# MCU.net
KiCad netlist of a schematic drawn in Altium Designer
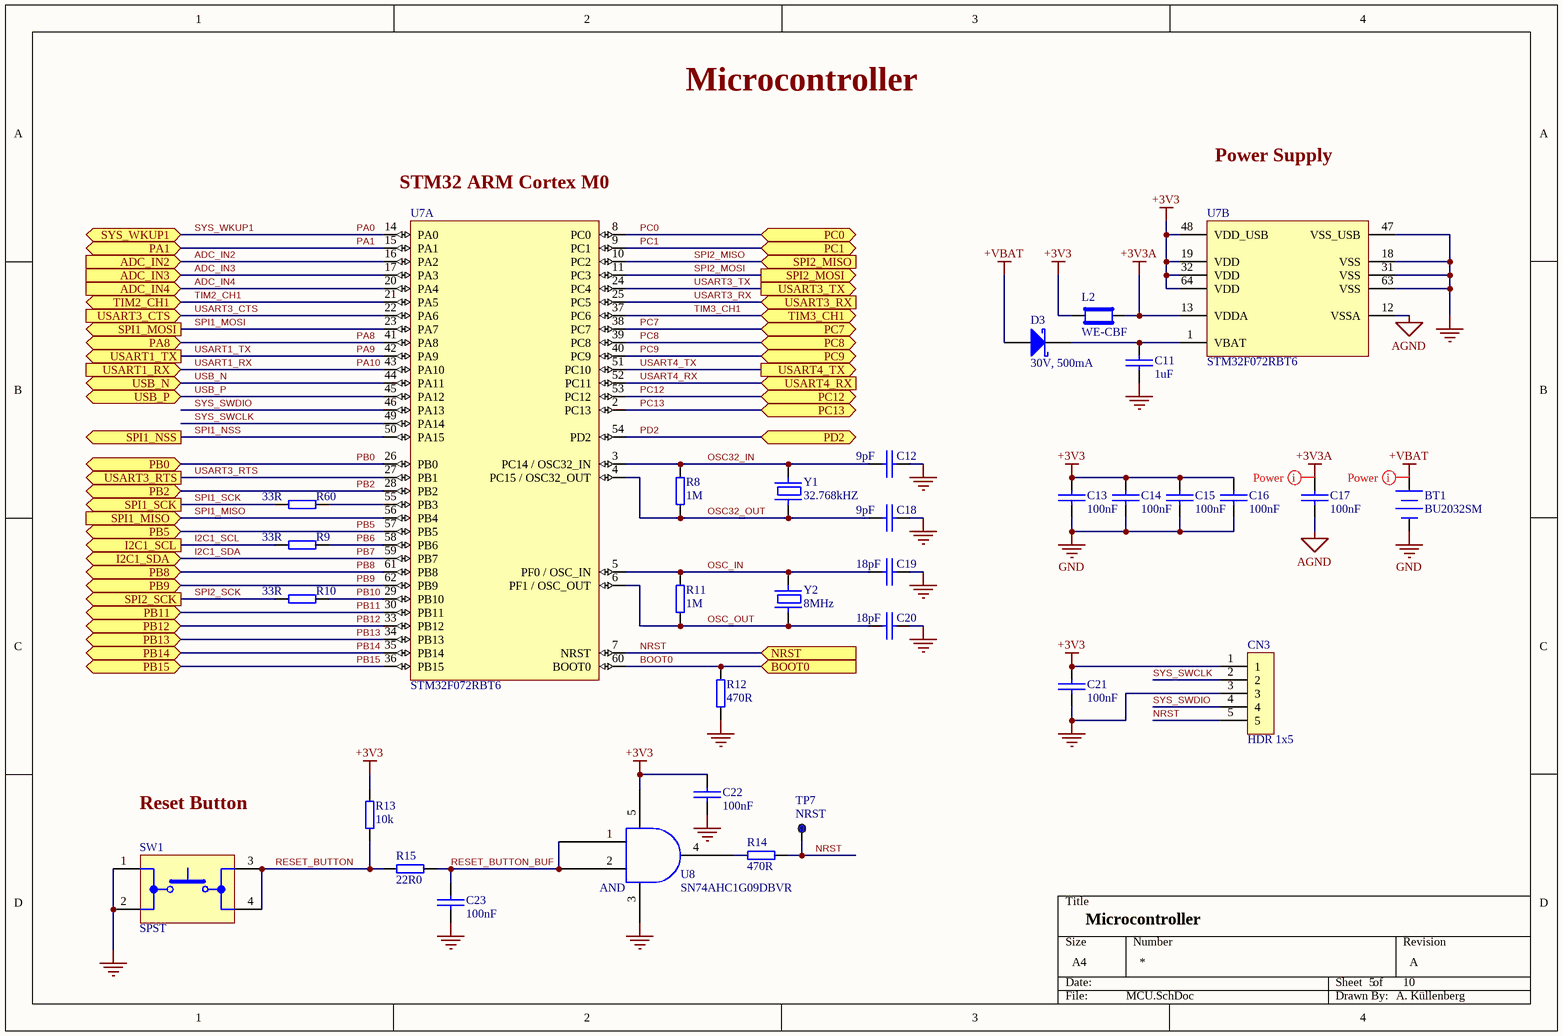
[diagram p0: MCU.SchDoc]

(export (version "E")
  (design (tool "Eeschema 10.0.6"))
  (components
    (comp (ref "BT1")
      (value "BU2032SM")
      (footprint "BU2032SM")
      (description "HOLDER CR2032 GOLD LEADS SMD")
      (fields
        (field (name "PART NUMBER") "BU2032SM-BT-GTR")
        (field (name "MANUFACTURER") "MPD (Memory Protection Devices)")
        (field (name "PUBLISHER") "Altium Limited")
      )
      (libsource (lib "AKLib") (part "Battery"))
    )
    (comp (ref "C11")
      (value "1uF")
      (footprint "C0603")
      (description "CAP CER 1UF 25V X7R 0603")
      (fields
        (field (name "PART NUMBER") "GCM188R71E105KA64D")
        (field (name "MANUFACTURER") "Murata Electronics North America")
      )
      (libsource (lib "AKLib") (part "CAP"))
    )
    (comp (ref "C12")
      (value "9pF")
      (footprint "C0603")
      (description "CAP CER 9PF 50V NP0 0603")
      (fields
        (field (name "PART NUMBER") "CL10C090DB8NNNC")
        (field (name "MANUFACTURER") "Samsung Electro-Mechanics America, Inc.")
      )
      (libsource (lib "AKLib") (part "CAP"))
    )
    (comp (ref "C13")
      (value "100nF")
      (footprint "C0603")
      (description "CAP CER 0.1UF 50V X7R 0603")
      (fields (field (name "PART NUMBER") "C0603C104K5RACTU") (field (name "MANUFACTURER") "Kemet"))
      (libsource (lib "AKLib") (part "CAP"))
    )
    (comp (ref "C14")
      (value "100nF")
      (footprint "C0603")
      (description "CAP CER 0.1UF 50V X7R 0603")
      (fields (field (name "PART NUMBER") "C0603C104K5RACTU") (field (name "MANUFACTURER") "Kemet"))
      (libsource (lib "AKLib") (part "CAP"))
    )
    (comp (ref "C15")
      (value "100nF")
      (footprint "C0603")
      (description "CAP CER 0.1UF 50V X7R 0603")
      (fields (field (name "PART NUMBER") "C0603C104K5RACTU") (field (name "MANUFACTURER") "Kemet"))
      (libsource (lib "AKLib") (part "CAP"))
    )
    (comp (ref "C16")
      (value "100nF")
      (footprint "C0603")
      (description "CAP CER 0.1UF 50V X7R 0603")
      (fields (field (name "PART NUMBER") "C0603C104K5RACTU") (field (name "MANUFACTURER") "Kemet"))
      (libsource (lib "AKLib") (part "CAP"))
    )
    (comp (ref "C17")
      (value "100nF")
      (footprint "C0603")
      (description "CAP CER 0.1UF 50V X7R 0603")
      (fields (field (name "PART NUMBER") "C0603C104K5RACTU") (field (name "MANUFACTURER") "Kemet"))
      (libsource (lib "AKLib") (part "CAP"))
    )
    (comp (ref "C18")
      (value "9pF")
      (footprint "C0603")
      (description "CAP CER 9PF 50V NP0 0603")
      (fields
        (field (name "PART NUMBER") "CL10C090DB8NNNC")
        (field (name "MANUFACTURER") "Samsung Electro-Mechanics America, Inc.")
      )
      (libsource (lib "AKLib") (part "CAP"))
    )
    (comp (ref "C19")
      (value "18pF")
      (footprint "C0603")
      (description "CAP CER 18PF 50V NP0 0603")
      (fields
        (field (name "PART NUMBER") "CL10C180JB8NNNC")
        (field (name "MANUFACTURER") "Samsung Electro-Mechanics America, Inc.")
      )
      (libsource (lib "AKLib") (part "CAP"))
    )
    (comp (ref "C20")
      (value "18pF")
      (footprint "C0603")
      (description "CAP CER 18PF 50V NP0 0603")
      (fields
        (field (name "PART NUMBER") "CL10C180JB8NNNC")
        (field (name "MANUFACTURER") "Samsung Electro-Mechanics America, Inc.")
      )
      (libsource (lib "AKLib") (part "CAP"))
    )
    (comp (ref "C21")
      (value "100nF")
      (footprint "C0603")
      (description "CAP CER 0.1UF 50V X7R 0603")
      (fields (field (name "PART NUMBER") "C0603C104K5RACTU") (field (name "MANUFACTURER") "Kemet"))
      (libsource (lib "AKLib") (part "CAP"))
    )
    (comp (ref "C22")
      (value "100nF")
      (footprint "C0603")
      (description "CAP CER 0.1UF 50V X7R 0603")
      (fields (field (name "PART NUMBER") "C0603C104K5RACTU") (field (name "MANUFACTURER") "Kemet"))
      (libsource (lib "AKLib") (part "CAP"))
    )
    (comp (ref "C23")
      (value "100nF")
      (footprint "C0603")
      (description "CAP CER 0.1UF 50V X7R 0603")
      (fields (field (name "PART NUMBER") "C0603C104K5RACTU") (field (name "MANUFACTURER") "Kemet"))
      (libsource (lib "AKLib") (part "CAP"))
    )
    (comp (ref "CN3")
      (value "HDR 1x5")
      (footprint "PREC005SAAN-RC")
      (description "CONN HEADER .100\" SNGL STR 5POS")
      (fields
        (field (name "PART NUMBER") "PREC005SAAN-RC")
        (field (name "MANUFACTURER") "Sullins Connector Solutions")
      )
      (libsource (lib "AKLib") (part "Header 1x5"))
    )
    (comp (ref "D3")
      (value "30V, 500mA")
      (footprint "SOD523_N")
      (description "DIODE SCHOTTKY 30V 500MA SC79-2")
      (fields
        (field (name "PART NUMBER") "BAS 3005B-02V H6327")
        (field (name "MANUFACTURER") "Infineon Technologies")
      )
      (libsource (lib "AKLib") (part "Schottky Diode"))
    )
    (comp (ref "L2")
      (value "WE-CBF")
      (footprint "L0603")
      (description "FERRITE BEAD 600 OHM 0603 1LN")
      (fields (field (name "PART NUMBER") "742792651") (field (name "MANUFACTURER") "Wurth Electronics Inc."))
      (libsource (lib "AKLib") (part "FBEAD"))
    )
    (comp (ref "R8")
      (value "1M")
      (footprint "R0603")
      (description "RES SMD 1M OHM 1% 1/10W 0603")
      (fields (field (name "PART NUMBER") "RC0603FR-071ML") (field (name "MANUFACTURER") "Yageo"))
      (libsource (lib "AKLib") (part "RES"))
    )
    (comp (ref "R9")
      (value "33R")
      (footprint "R0402")
      (description "RES SMD 33 OHM 1% 1/16W 0402")
      (fields (field (name "PART NUMBER") "RC0402FR-0733RL") (field (name "MANUFACTURER") "Yageo"))
      (libsource (lib "AKLib") (part "RES"))
    )
    (comp (ref "R10")
      (value "33R")
      (footprint "R0402")
      (description "RES SMD 33 OHM 1% 1/16W 0402")
      (fields (field (name "PART NUMBER") "RC0402FR-0733RL") (field (name "MANUFACTURER") "Yageo"))
      (libsource (lib "AKLib") (part "RES"))
    )
    (comp (ref "R11")
      (value "1M")
      (footprint "R0603")
      (description "RES SMD 1M OHM 1% 1/10W 0603")
      (fields (field (name "PART NUMBER") "RC0603FR-071ML") (field (name "MANUFACTURER") "Yageo"))
      (libsource (lib "AKLib") (part "RES"))
    )
    (comp (ref "R12")
      (value "470R")
      (footprint "R0402")
      (description "RES SMD 470 OHM 1% 1/16W 0402")
      (fields (field (name "PART NUMBER") "RC0402FR-07470RL") (field (name "MANUFACTURER") "Yageo"))
      (libsource (lib "AKLib") (part "RES"))
    )
    (comp (ref "R13")
      (value "10k")
      (footprint "R0603")
      (description "RES SMD 10K OHM 1% 1/10W 0603")
      (fields (field (name "PART NUMBER") "RC0603FR-0710KL") (field (name "MANUFACTURER") "Yageo"))
      (libsource (lib "AKLib") (part "RES"))
    )
    (comp (ref "R14")
      (value "470R")
      (footprint "R0603")
      (description "RES SMD 470 OHM 1% 1/10W 0603")
      (fields
        (field (name "MANUFACTURER") "Yageo")
        (field (name "MANUFACTURER PART NUMBER") "RC0603FR-07470RL")
      )
      (libsource (lib "AKLib") (part "RES"))
    )
    (comp (ref "R15")
      (value "22R0")
      (footprint "R0603")
      (description "RES SMD 22 OHM 1% 1/10W 0603")
      (fields (field (name "PART NUMBER") "RC0603FR-0722RL") (field (name "MANUFACTURER") "Yageo"))
      (libsource (lib "AKLib") (part "RES"))
    )
    (comp (ref "R60")
      (value "33R")
      (footprint "R0402")
      (description "RES SMD 33 OHM 1% 1/16W 0402")
      (fields (field (name "PART NUMBER") "RC0402FR-0733RL") (field (name "MANUFACTURER") "Yageo"))
      (libsource (lib "AKLib") (part "RES"))
    )
    (comp (ref "SW1")
      (value "SPST")
      (footprint "1825910-6")
      (description "SWITCH TACTILE SPST-NO 0.05A 24V")
      (fields
        (field (name "PART NUMBER") "1825910-6")
        (field (name "MANUFACTURER") "TE Connectivity ALCOSWITCH Switches")
      )
      (libsource (lib "AKLib") (part "1825910-6"))
    )
    (comp (ref "TP7")
      (value "NRST")
      (footprint "TP_1mm")
      (fields (field (name "PART NUMBER") "TP"))
      (libsource (lib "AKLib") (part "TP"))
    )
    (comp (ref "U7")
      (value "STM32F072RBT6")
      (footprint "LQFP64")
      (description "IC MCU 32BIT 128KB FLASH 64LQFP")
      (fields (field (name "MANUFACTURER") "STMicroelectronics"))
      (libsource (lib "AKLib") (part "STM32F072RBT6"))
    )
    (comp (ref "U8")
      (value "SN74AHC1G09DBVR")
      (footprint "SOT23-5")
      (description "IC GATE AND 1CH 2-INP SOT-23-5")
      (fields (field (name "MANUFACTURER") "Texas Instruments"))
      (libsource (lib "AKLib") (part "SN74AHC1G09DBVR"))
    )
    (comp (ref "Y1")
      (value "32.768kHZ")
      (footprint "ABS07AIG")
      (description "CRYSTAL 32.768KHZ 9PF SMD")
      (fields
        (field (name "PART NUMBER") "ABS07AIG-32.768KHZ-9-1-T")
        (field (name "MANUFACTURER") "Abracon LLC")
      )
      (libsource (lib "AKLib") (part "XTAL"))
    )
    (comp (ref "Y2")
      (value "8MHz")
      (footprint "ABM7_v1_1_BIG")
      (description "CRYSTAL 8.0000MHZ 18PF SMD")
      (fields (field (name "PART NUMBER") "ABM7-8.000MHZ-D2Y-T") (field (name "MANUFACTURER") "Abracon LLC"))
      (libsource (lib "AKLib") (part "XTAL"))
    )
  )
  (nets
    (net (code "1") (name "+3V3") (class "Default")
      (node (ref "C13") (pin "2") (pinfunction "2_2") (pintype "passive"))
      (node (ref "C14") (pin "2") (pinfunction "2_2") (pintype "passive"))
      (node (ref "C15") (pin "2") (pinfunction "2_2") (pintype "passive"))
      (node (ref "C16") (pin "2") (pinfunction "2_2") (pintype "passive"))
      (node (ref "C21") (pin "2") (pinfunction "2_2") (pintype "passive"))
      (node (ref "C22") (pin "2") (pinfunction "2_2") (pintype "passive"))
      (node (ref "CN3") (pin "1") (pinfunction "1_1") (pintype "passive"))
      (node (ref "L2") (pin "1") (pinfunction "1_1") (pintype "passive"))
      (node (ref "R13") (pin "2") (pinfunction "2_2") (pintype "passive"))
      (node (ref "U7") (pin "19") (pinfunction "VDD_19") (pintype "power_in"))
      (node (ref "U7") (pin "32") (pinfunction "VDD_32") (pintype "power_in"))
      (node (ref "U7") (pin "48") (pinfunction "VDD_USB_48") (pintype "power_in"))
      (node (ref "U7") (pin "64") (pinfunction "VDD_64") (pintype "power_in"))
      (node (ref "U8") (pin "5") (pinfunction "5_5") (pintype "passive"))
    )
    (net (code "2") (name "+3V3A") (class "Default")
      (node (ref "C17") (pin "2") (pinfunction "2_2") (pintype "passive"))
      (node (ref "L2") (pin "2") (pinfunction "2_2") (pintype "passive"))
      (node (ref "U7") (pin "13") (pinfunction "VDDA_13") (pintype "power_in"))
    )
    (net (code "3") (name "+VBAT") (class "Default")
      (node (ref "BT1") (pin "1") (pinfunction "+_1") (pintype "passive"))
      (node (ref "D3") (pin "1") (pinfunction "A_1") (pintype "passive"))
    )
    (net (code "4") (name "/ADC_IN2") (class "Default")
      (node (ref "U7") (pin "16") (pinfunction "PA2_16") (pintype "bidirectional"))
    )
    (net (code "5") (name "/ADC_IN3") (class "Default")
      (node (ref "U7") (pin "17") (pinfunction "PA3_17") (pintype "bidirectional"))
    )
    (net (code "6") (name "/ADC_IN4") (class "Default")
      (node (ref "U7") (pin "20") (pinfunction "PA4_20") (pintype "bidirectional"))
    )
    (net (code "7") (name "/BOOT0") (class "Default")
      (node (ref "R12") (pin "2") (pinfunction "2_2") (pintype "passive"))
      (node (ref "U7") (pin "60") (pinfunction "BOOT0_60") (pintype "bidirectional"))
    )
    (net (code "8") (name "/I2C1_SCL") (class "Default")
      (node (ref "R9") (pin "1") (pinfunction "1_1") (pintype "passive"))
    )
    (net (code "9") (name "/I2C1_SDA") (class "Default")
      (node (ref "U7") (pin "59") (pinfunction "PB7_59") (pintype "bidirectional"))
    )
    (net (code "10") (name "/NRST") (class "Default")
      (node (ref "CN3") (pin "5") (pinfunction "5_5") (pintype "passive"))
      (node (ref "R14") (pin "2") (pinfunction "2_2") (pintype "passive"))
      (node (ref "TP7") (pin "1") (pinfunction "1_1") (pintype "passive"))
      (node (ref "U7") (pin "7") (pinfunction "NRST_7") (pintype "bidirectional"))
    )
    (net (code "11") (name "/OSC32_IN") (class "Default")
      (node (ref "C12") (pin "1") (pinfunction "1_1") (pintype "passive"))
      (node (ref "R8") (pin "2") (pinfunction "2_2") (pintype "passive"))
      (node (ref "U7") (pin "3") (pinfunction "PC14_/_OSC32_IN_3") (pintype "bidirectional"))
      (node (ref "Y1") (pin "2") (pinfunction "2_2") (pintype "passive"))
    )
    (net (code "12") (name "/OSC32_OUT") (class "Default")
      (node (ref "C18") (pin "1") (pinfunction "1_1") (pintype "passive"))
      (node (ref "R8") (pin "1") (pinfunction "1_1") (pintype "passive"))
      (node (ref "U7") (pin "4") (pinfunction "PC15_/_OSC32_OUT_4") (pintype "bidirectional"))
      (node (ref "Y1") (pin "1") (pinfunction "1_1") (pintype "passive"))
    )
    (net (code "13") (name "/OSC_IN") (class "Default")
      (node (ref "C19") (pin "1") (pinfunction "1_1") (pintype "passive"))
      (node (ref "R11") (pin "2") (pinfunction "2_2") (pintype "passive"))
      (node (ref "U7") (pin "5") (pinfunction "PF0_/_OSC_IN_5") (pintype "bidirectional"))
      (node (ref "Y2") (pin "2") (pinfunction "2_2") (pintype "passive"))
    )
    (net (code "14") (name "/OSC_OUT") (class "Default")
      (node (ref "C20") (pin "1") (pinfunction "1_1") (pintype "passive"))
      (node (ref "R11") (pin "1") (pinfunction "1_1") (pintype "passive"))
      (node (ref "U7") (pin "6") (pinfunction "PF1_/_OSC_OUT_6") (pintype "bidirectional"))
      (node (ref "Y2") (pin "1") (pinfunction "1_1") (pintype "passive"))
    )
    (net (code "15") (name "/PA0") (class "Default")
      (node (ref "U7") (pin "14") (pinfunction "PA0_14") (pintype "bidirectional"))
    )
    (net (code "16") (name "/PA1") (class "Default")
      (node (ref "U7") (pin "15") (pinfunction "PA1_15") (pintype "bidirectional"))
    )
    (net (code "17") (name "/PA8") (class "Default")
      (node (ref "U7") (pin "41") (pinfunction "PA8_41") (pintype "bidirectional"))
    )
    (net (code "18") (name "/PA9") (class "Default")
      (node (ref "U7") (pin "42") (pinfunction "PA9_42") (pintype "bidirectional"))
    )
    (net (code "19") (name "/PA10") (class "Default")
      (node (ref "U7") (pin "43") (pinfunction "PA10_43") (pintype "bidirectional"))
    )
    (net (code "20") (name "/PB0") (class "Default")
      (node (ref "U7") (pin "26") (pinfunction "PB0_26") (pintype "bidirectional"))
    )
    (net (code "21") (name "/PB2") (class "Default")
      (node (ref "U7") (pin "28") (pinfunction "PB2_28") (pintype "bidirectional"))
    )
    (net (code "22") (name "/PB5") (class "Default")
      (node (ref "U7") (pin "57") (pinfunction "PB5_57") (pintype "bidirectional"))
    )
    (net (code "23") (name "/PB6") (class "Default")
      (node (ref "R9") (pin "2") (pinfunction "2_2") (pintype "passive"))
      (node (ref "U7") (pin "58") (pinfunction "PB6_58") (pintype "bidirectional"))
    )
    (net (code "24") (name "/PB8") (class "Default")
      (node (ref "U7") (pin "61") (pinfunction "PB8_61") (pintype "bidirectional"))
    )
    (net (code "25") (name "/PB9") (class "Default")
      (node (ref "U7") (pin "62") (pinfunction "PB9_62") (pintype "bidirectional"))
    )
    (net (code "26") (name "/PB10") (class "Default")
      (node (ref "R10") (pin "2") (pinfunction "2_2") (pintype "passive"))
      (node (ref "U7") (pin "29") (pinfunction "PB10_29") (pintype "bidirectional"))
    )
    (net (code "27") (name "/PB11") (class "Default")
      (node (ref "U7") (pin "30") (pinfunction "PB11_30") (pintype "bidirectional"))
    )
    (net (code "28") (name "/PB12") (class "Default")
      (node (ref "U7") (pin "33") (pinfunction "PB12_33") (pintype "bidirectional"))
    )
    (net (code "29") (name "/PB13") (class "Default")
      (node (ref "U7") (pin "34") (pinfunction "PB13_34") (pintype "bidirectional"))
    )
    (net (code "30") (name "/PB14") (class "Default")
      (node (ref "U7") (pin "35") (pinfunction "PB14_35") (pintype "bidirectional"))
    )
    (net (code "31") (name "/PB15") (class "Default")
      (node (ref "U7") (pin "36") (pinfunction "PB15_36") (pintype "bidirectional"))
    )
    (net (code "32") (name "/PC0") (class "Default")
      (node (ref "U7") (pin "8") (pinfunction "PC0_8") (pintype "bidirectional"))
    )
    (net (code "33") (name "/PC1") (class "Default")
      (node (ref "U7") (pin "9") (pinfunction "PC1_9") (pintype "bidirectional"))
    )
    (net (code "34") (name "/PC7") (class "Default")
      (node (ref "U7") (pin "38") (pinfunction "PC7_38") (pintype "bidirectional"))
    )
    (net (code "35") (name "/PC8") (class "Default")
      (node (ref "U7") (pin "39") (pinfunction "PC8_39") (pintype "bidirectional"))
    )
    (net (code "36") (name "/PC9") (class "Default")
      (node (ref "U7") (pin "40") (pinfunction "PC9_40") (pintype "bidirectional"))
    )
    (net (code "37") (name "/PC12") (class "Default")
      (node (ref "U7") (pin "53") (pinfunction "PC12_53") (pintype "bidirectional"))
    )
    (net (code "38") (name "/PC13") (class "Default")
      (node (ref "U7") (pin "2") (pinfunction "PC13_2") (pintype "bidirectional"))
    )
    (net (code "39") (name "/PD2") (class "Default")
      (node (ref "U7") (pin "54") (pinfunction "PD2_54") (pintype "bidirectional"))
    )
    (net (code "40") (name "/RESET_BUTTON") (class "Default")
      (node (ref "R13") (pin "1") (pinfunction "1_1") (pintype "passive"))
      (node (ref "R15") (pin "1") (pinfunction "1_1") (pintype "passive"))
      (node (ref "SW1") (pin "3") (pinfunction "3_3") (pintype "passive"))
      (node (ref "SW1") (pin "4") (pinfunction "4_4") (pintype "passive"))
    )
    (net (code "41") (name "/RESET_BUTTON_BUF") (class "Default")
      (node (ref "C23") (pin "2") (pinfunction "2_2") (pintype "passive"))
      (node (ref "R15") (pin "2") (pinfunction "2_2") (pintype "passive"))
      (node (ref "U8") (pin "1") (pinfunction "1_1") (pintype "passive"))
      (node (ref "U8") (pin "2") (pinfunction "2_2") (pintype "passive"))
    )
    (net (code "42") (name "/SPI1_MISO") (class "Default")
      (node (ref "U7") (pin "56") (pinfunction "PB4_56") (pintype "bidirectional"))
    )
    (net (code "43") (name "/SPI1_MOSI") (class "Default")
      (node (ref "U7") (pin "23") (pinfunction "PA7_23") (pintype "bidirectional"))
    )
    (net (code "44") (name "/SPI1_NSS") (class "Default")
      (node (ref "U7") (pin "50") (pinfunction "PA15_50") (pintype "bidirectional"))
    )
    (net (code "45") (name "/SPI1_SCK") (class "Default")
      (node (ref "R60") (pin "1") (pinfunction "1_1") (pintype "passive"))
    )
    (net (code "46") (name "/SPI2_MISO") (class "Default")
      (node (ref "U7") (pin "10") (pinfunction "PC2_10") (pintype "bidirectional"))
    )
    (net (code "47") (name "/SPI2_MOSI") (class "Default")
      (node (ref "U7") (pin "11") (pinfunction "PC3_11") (pintype "bidirectional"))
    )
    (net (code "48") (name "/SPI2_SCK") (class "Default")
      (node (ref "R10") (pin "1") (pinfunction "1_1") (pintype "passive"))
    )
    (net (code "49") (name "/SYS_SWCLK") (class "Default")
      (node (ref "CN3") (pin "2") (pinfunction "2_2") (pintype "passive"))
      (node (ref "U7") (pin "49") (pinfunction "PA14_49") (pintype "bidirectional"))
    )
    (net (code "50") (name "/SYS_SWDIO") (class "Default")
      (node (ref "CN3") (pin "4") (pinfunction "4_4") (pintype "passive"))
      (node (ref "U7") (pin "46") (pinfunction "PA13_46") (pintype "bidirectional"))
    )
    (net (code "51") (name "/TIM2_CH1") (class "Default")
      (node (ref "U7") (pin "21") (pinfunction "PA5_21") (pintype "bidirectional"))
    )
    (net (code "52") (name "/TIM3_CH1") (class "Default")
      (node (ref "U7") (pin "37") (pinfunction "PC6_37") (pintype "bidirectional"))
    )
    (net (code "53") (name "/USART3_CTS") (class "Default")
      (node (ref "U7") (pin "22") (pinfunction "PA6_22") (pintype "bidirectional"))
    )
    (net (code "54") (name "/USART3_RTS") (class "Default")
      (node (ref "U7") (pin "27") (pinfunction "PB1_27") (pintype "bidirectional"))
    )
    (net (code "55") (name "/USART3_RX") (class "Default")
      (node (ref "U7") (pin "25") (pinfunction "PC5_25") (pintype "bidirectional"))
    )
    (net (code "56") (name "/USART3_TX") (class "Default")
      (node (ref "U7") (pin "24") (pinfunction "PC4_24") (pintype "bidirectional"))
    )
    (net (code "57") (name "/USART4_RX") (class "Default")
      (node (ref "U7") (pin "52") (pinfunction "PC11_52") (pintype "bidirectional"))
    )
    (net (code "58") (name "/USART4_TX") (class "Default")
      (node (ref "U7") (pin "51") (pinfunction "PC10_51") (pintype "bidirectional"))
    )
    (net (code "59") (name "/USB_N") (class "Default")
      (node (ref "U7") (pin "44") (pinfunction "PA11_44") (pintype "bidirectional"))
    )
    (net (code "60") (name "/USB_P") (class "Default")
      (node (ref "U7") (pin "45") (pinfunction "PA12_45") (pintype "bidirectional"))
    )
    (net (code "61") (name "AGND") (class "Default")
      (node (ref "C17") (pin "1") (pinfunction "1_1") (pintype "passive"))
      (node (ref "U7") (pin "12") (pinfunction "VSSA_12") (pintype "power_in"))
    )
    (net (code "62") (name "GND") (class "Default")
      (node (ref "BT1") (pin "2") (pinfunction "-_2") (pintype "passive"))
      (node (ref "C11") (pin "1") (pinfunction "1_1") (pintype "passive"))
      (node (ref "C12") (pin "2") (pinfunction "2_2") (pintype "passive"))
      (node (ref "C13") (pin "1") (pinfunction "1_1") (pintype "passive"))
      (node (ref "C14") (pin "1") (pinfunction "1_1") (pintype "passive"))
      (node (ref "C15") (pin "1") (pinfunction "1_1") (pintype "passive"))
      (node (ref "C16") (pin "1") (pinfunction "1_1") (pintype "passive"))
      (node (ref "C18") (pin "2") (pinfunction "2_2") (pintype "passive"))
      (node (ref "C19") (pin "2") (pinfunction "2_2") (pintype "passive"))
      (node (ref "C20") (pin "2") (pinfunction "2_2") (pintype "passive"))
      (node (ref "C21") (pin "1") (pinfunction "1_1") (pintype "passive"))
      (node (ref "C22") (pin "1") (pinfunction "1_1") (pintype "passive"))
      (node (ref "C23") (pin "1") (pinfunction "1_1") (pintype "passive"))
      (node (ref "CN3") (pin "3") (pinfunction "3_3") (pintype "passive"))
      (node (ref "R12") (pin "1") (pinfunction "1_1") (pintype "passive"))
      (node (ref "SW1") (pin "1") (pinfunction "1_1") (pintype "passive"))
      (node (ref "SW1") (pin "2") (pinfunction "2_2") (pintype "passive"))
      (node (ref "U7") (pin "18") (pinfunction "VSS_18") (pintype "power_in"))
      (node (ref "U7") (pin "31") (pinfunction "VSS_31") (pintype "power_in"))
      (node (ref "U7") (pin "47") (pinfunction "VSS_USB_47") (pintype "power_in"))
      (node (ref "U7") (pin "63") (pinfunction "VSS_63") (pintype "power_in"))
      (node (ref "U8") (pin "3") (pinfunction "3_3") (pintype "passive"))
    )
    (net (code "63") (name "Net-(D3-K)") (class "Default")
      (node (ref "C11") (pin "2") (pinfunction "2_2") (pintype "passive"))
      (node (ref "D3") (pin "2") (pinfunction "K_2") (pintype "passive"))
      (node (ref "U7") (pin "1") (pinfunction "VBAT_1") (pintype "power_in"))
    )
    (net (code "64") (name "Net-(R14-Pad1)") (class "Default")
      (node (ref "R14") (pin "1") (pinfunction "1_1") (pintype "passive"))
      (node (ref "U8") (pin "4") (pinfunction "4_4") (pintype "passive"))
    )
    (net (code "65") (name "Net-(U7A-PB3)") (class "Default")
      (node (ref "R60") (pin "2") (pinfunction "2_2") (pintype "passive"))
      (node (ref "U7") (pin "55") (pinfunction "PB3_55") (pintype "bidirectional"))
    )
  )
)
